# Power1.net
KiCad netlist of a schematic drawn in Altium Designer
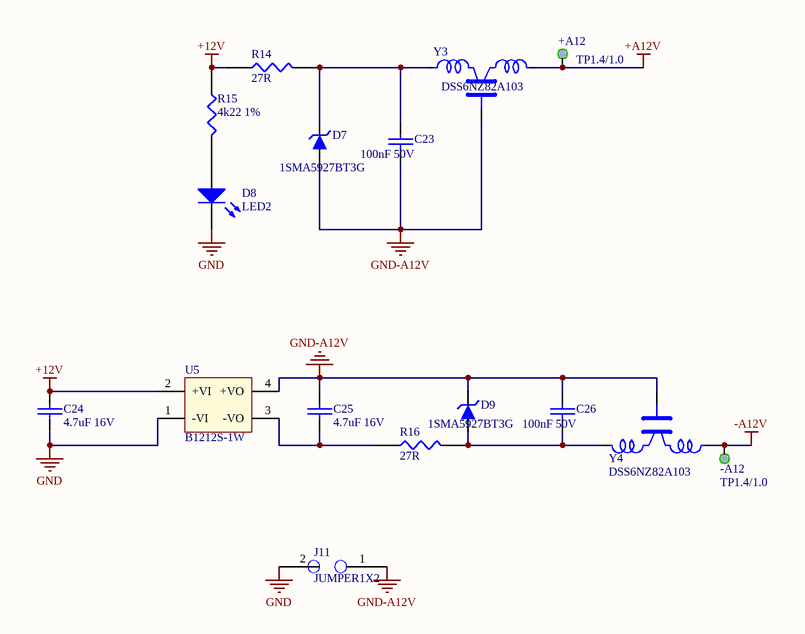
[diagram p0: Power1.SchDoc]

(export (version "E")
  (design (tool "Eeschema 10.0.6"))
  (components
    (comp (ref "+A12")
      (value "TP1.4/1.0")
      (footprint "UserPcbLib:TP1.4/1.0")
      (libsource (lib "UserSchlib") (part "TP1.4/1.0"))
    )
    (comp (ref "-A12")
      (value "TP1.4/1.0")
      (footprint "UserPcbLib:TP1.4/1.0")
      (libsource (lib "UserSchlib") (part "TP1.4/1.0"))
    )
    (comp (ref "C23")
      (value "100nF 50V")
      (footprint "IPC-7352 Chip_Capacitor_N:CAPC2012N")
      (libsource (lib "*") (part "CAP"))
    )
    (comp (ref "C24")
      (value "4.7uF 16V")
      (footprint "IPC-7352 Chip_Capacitor_N:CAPC2012N")
      (description "Capacitor")
      (libsource (lib "*") (part "CAP"))
    )
    (comp (ref "C25")
      (value "4.7uF 16V")
      (footprint "IPC-7352 Chip_Capacitor_N:CAPC2012N")
      (description "Capacitor")
      (libsource (lib "*") (part "CAP"))
    )
    (comp (ref "C26")
      (value "100nF 50V")
      (footprint "IPC-7352 Chip_Capacitor_N:CAPC2012N")
      (libsource (lib "*") (part "CAP"))
    )
    (comp (ref "D7")
      (value "1SMA5927BT3G")
      (footprint "Small Outline Diode - 2 C-Bend Leads:DSO-C2/X1.8")
      (description "Zener diode")
      (fields (field (name "MANUFACTURER") "ON"))
      (libsource (lib "UserSchlib") (part "Zener unidirectional"))
    )
    (comp (ref "D8")
      (value "LED2")
      (footprint "3.2X1.6X1.1")
      (description "Typical RED, GREEN, YELLOW, AMBER GaAs LED")
      (fields (field (name "PUBLISHER") "Altium Limited"))
      (libsource (lib "Miscellaneous Devices") (part "LED2"))
    )
    (comp (ref "D9")
      (value "1SMA5927BT3G")
      (footprint "Small Outline Diode - 2 C-Bend Leads:DSO-C2/X1.8")
      (description "Zener diode")
      (fields (field (name "MANUFACTURER") "ON"))
      (libsource (lib "UserSchlib") (part "Zener unidirectional"))
    )
    (comp (ref "J11")
      (value "JUMPER1X2")
      (footprint "UserPcbLib:JP-SOLDER-H1X2-3X2")
      (libsource (lib "Peter") (part "JUMPER1X2"))
    )
    (comp (ref "R14")
      (value "27R")
      (footprint "IPC-7352 Chip_Resistor_N:RESC3216N")
      (libsource (lib "*") (part "RES1"))
    )
    (comp (ref "R15")
      (value "4k22 1%")
      (footprint "IPC-7352 Chip_Resistor_N:RESC2012N")
      (libsource (lib "*") (part "RES1"))
    )
    (comp (ref "R16")
      (value "27R")
      (footprint "IPC-7352 Chip_Resistor_N:RESC3216N")
      (libsource (lib "*") (part "RES1"))
    )
    (comp (ref "U5")
      (value "B1212S-1W")
      (footprint "UserPcbLib:B0505S-W1")
      (description "12V isolated DC-DC converter")
      (libsource (lib "UserSchlib") (part "B0505S-1W"))
    )
    (comp (ref "Y3")
      (value "DSS6NZ82A103")
      (footprint "UserPcbLib:DSS6")
      (description "Murata EMI suppression filter")
      (fields (field (name "MANUFACTURER") "Murata"))
      (libsource (lib "UserSchlib") (part "DSS6"))
    )
    (comp (ref "Y4")
      (value "DSS6NZ82A103")
      (footprint "UserPcbLib:DSS6")
      (description "Murata EMI suppression filter")
      (fields (field (name "MANUFACTURER") "Murata"))
      (libsource (lib "UserSchlib") (part "DSS6"))
    )
  )
  (nets
    (net (code "1") (name "+12V") (class "Default")
      (node (ref "C24") (pin "1") (pintype "passive"))
      (node (ref "R14") (pin "1") (pinfunction "1_1") (pintype "passive"))
      (node (ref "R15") (pin "1") (pinfunction "1_1") (pintype "passive"))
      (node (ref "U5") (pin "2") (pinfunction "+VI_2") (pintype "passive"))
    )
    (net (code "2") (name "+A12V") (class "Default")
      (node (ref "+A12") (pin "1") (pinfunction "1_1") (pintype "passive"))
      (node (ref "Y3") (pin "3") (pinfunction "3_3") (pintype "passive"))
    )
    (net (code "3") (name "-A12V") (class "Default")
      (node (ref "-A12") (pin "1") (pinfunction "1_1") (pintype "passive"))
      (node (ref "Y4") (pin "1") (pinfunction "1_1") (pintype "passive"))
    )
    (net (code "4") (name "GND") (class "Default")
      (node (ref "C24") (pin "2") (pintype "passive"))
      (node (ref "D8") (pin "2") (pinfunction "K_2") (pintype "passive"))
      (node (ref "J11") (pin "2") (pinfunction "1_2") (pintype "passive"))
      (node (ref "U5") (pin "1") (pinfunction "-VI_1") (pintype "passive"))
    )
    (net (code "5") (name "GND-A12V") (class "Default")
      (node (ref "C23") (pin "1") (pintype "passive"))
      (node (ref "C25") (pin "1") (pintype "passive"))
      (node (ref "C26") (pin "2") (pintype "passive"))
      (node (ref "D7") (pin "1") (pinfunction "A_1") (pintype "passive"))
      (node (ref "D9") (pin "2") (pinfunction "K_2") (pintype "passive"))
      (node (ref "J11") (pin "1") (pinfunction "0_1") (pintype "passive"))
      (node (ref "U5") (pin "4") (pinfunction "+VO_4") (pintype "passive"))
      (node (ref "Y3") (pin "2") (pinfunction "2_2") (pintype "passive"))
      (node (ref "Y4") (pin "2") (pinfunction "2_2") (pintype "passive"))
    )
    (net (code "6") (name "Net-(D7-K)") (class "Default")
      (node (ref "C23") (pin "2") (pintype "passive"))
      (node (ref "D7") (pin "2") (pinfunction "K_2") (pintype "passive"))
      (node (ref "R14") (pin "2") (pinfunction "2_2") (pintype "passive"))
      (node (ref "Y3") (pin "1") (pinfunction "1_1") (pintype "passive"))
    )
    (net (code "7") (name "Net-(D8-A)") (class "Default")
      (node (ref "D8") (pin "1") (pinfunction "A_1") (pintype "passive"))
      (node (ref "R15") (pin "2") (pinfunction "2_2") (pintype "passive"))
    )
    (net (code "8") (name "Net-(D9-A)") (class "Default")
      (node (ref "C26") (pin "1") (pintype "passive"))
      (node (ref "D9") (pin "1") (pinfunction "A_1") (pintype "passive"))
      (node (ref "R16") (pin "2") (pinfunction "2_2") (pintype "passive"))
      (node (ref "Y4") (pin "3") (pinfunction "3_3") (pintype "passive"))
    )
    (net (code "9") (name "Net-(U5--VO)") (class "Default")
      (node (ref "C25") (pin "2") (pintype "passive"))
      (node (ref "R16") (pin "1") (pinfunction "1_1") (pintype "passive"))
      (node (ref "U5") (pin "3") (pinfunction "-VO_3") (pintype "passive"))
    )
  )
)
